# TDT_BreakoutBrd.net
KiCad netlist of a schematic drawn in EAGLE
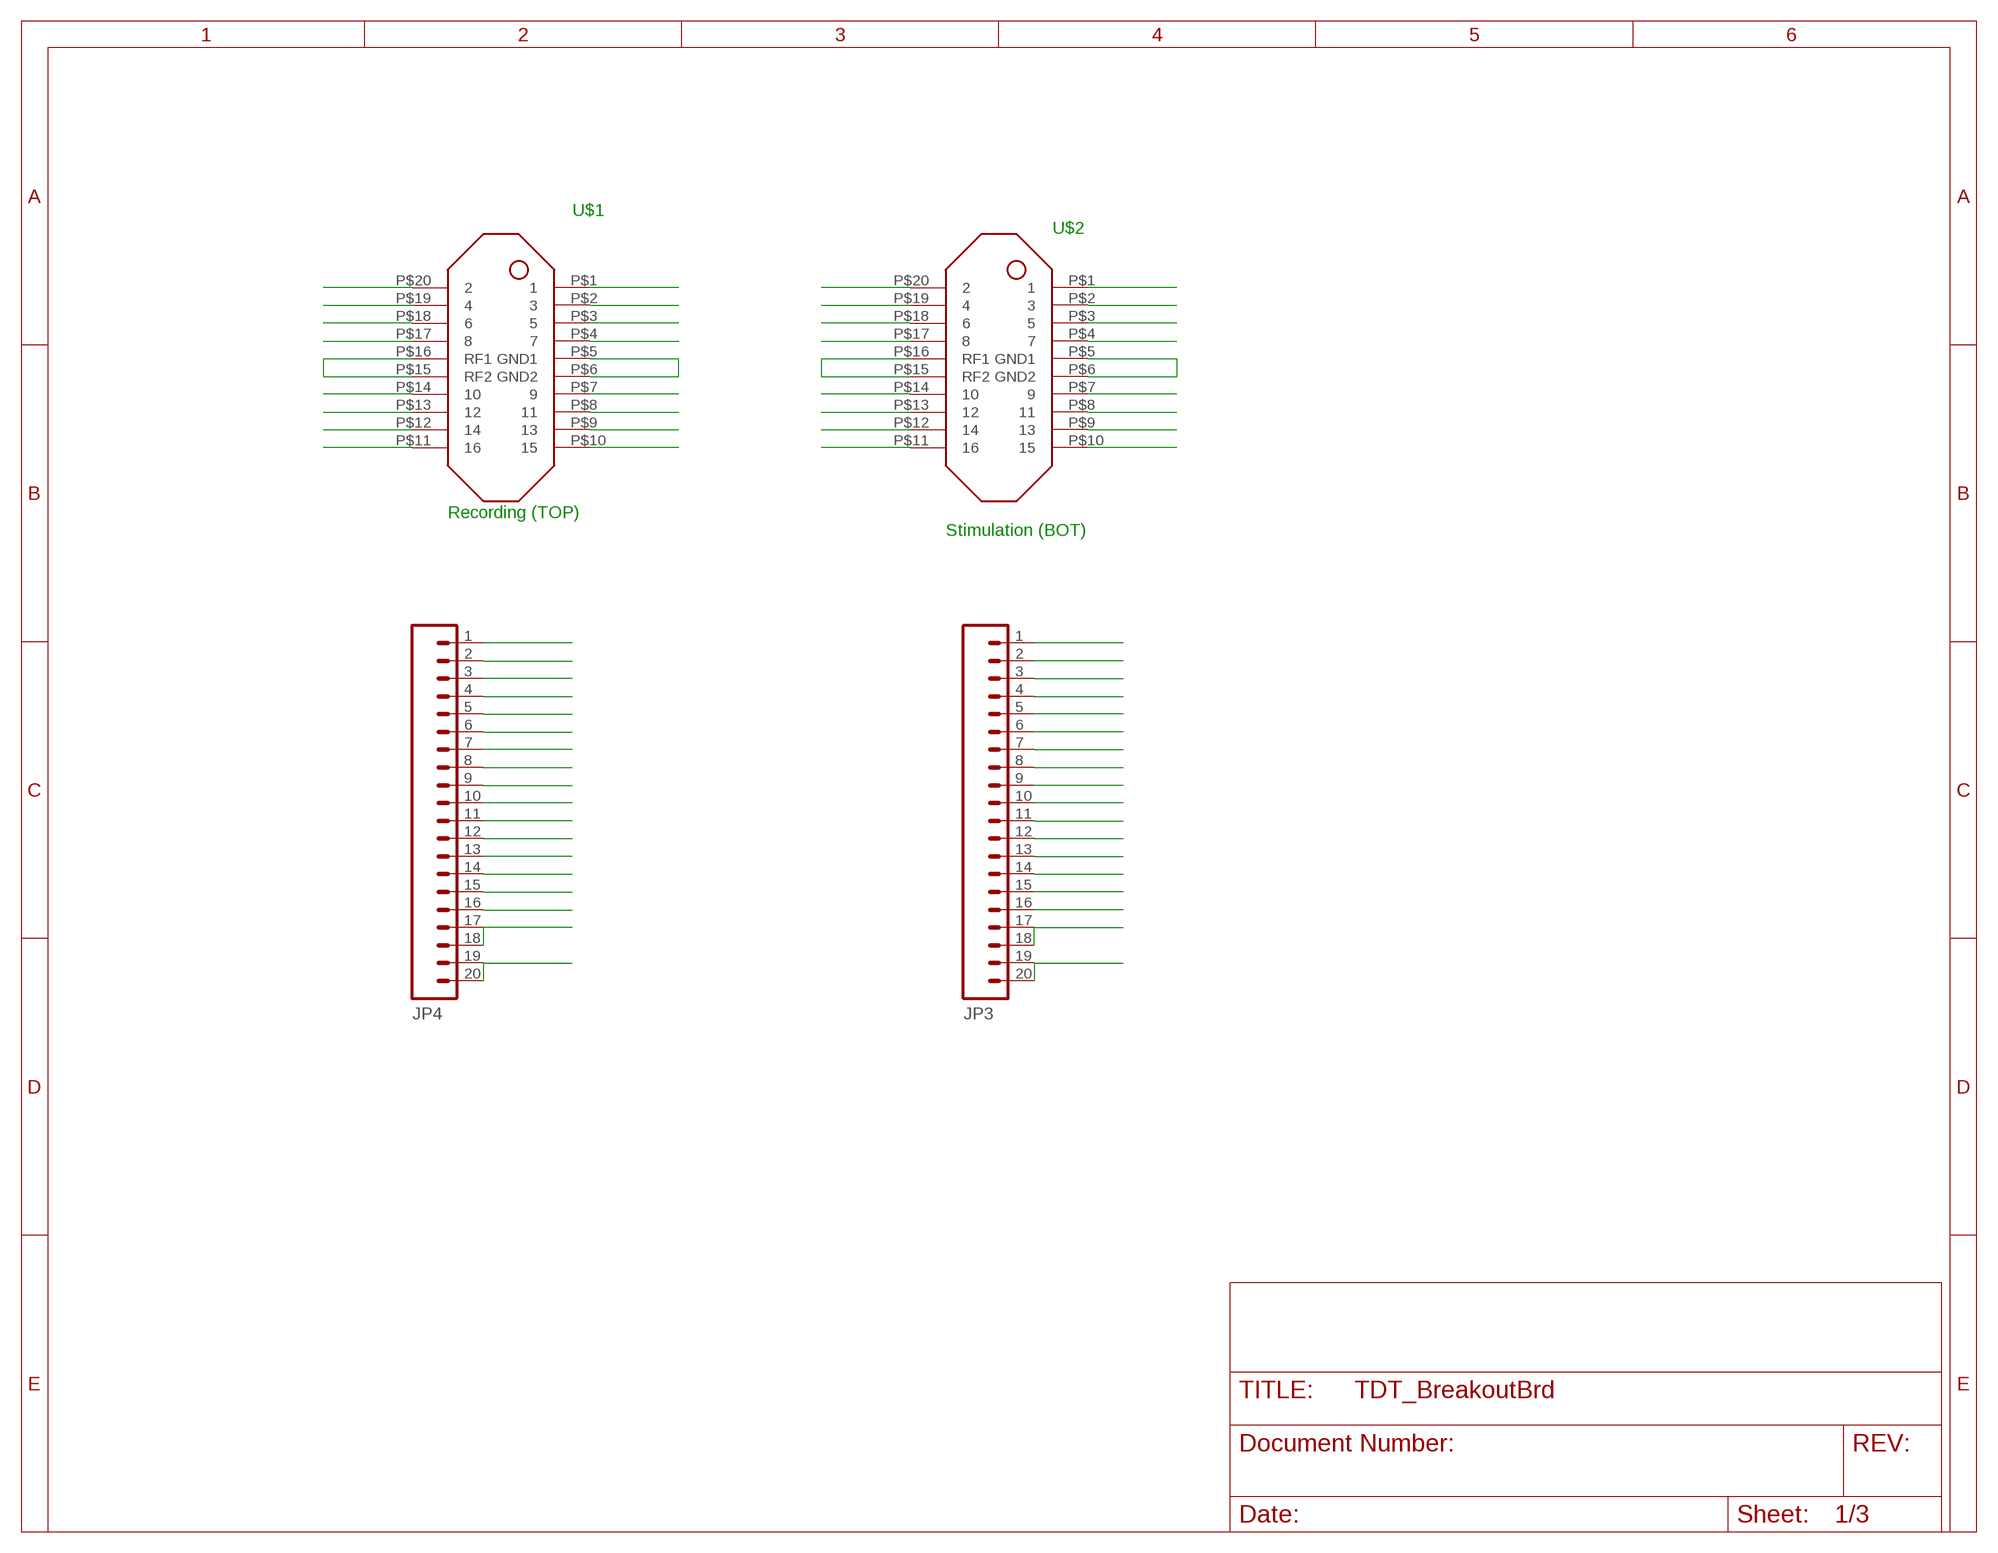
[diagram p0: schematic, sheet 1]

(export (version "E")
  (design (tool "Eeschema 10.0.6"))
  (components
    (comp (ref "JP3")
      (value "M20")
      (footprint "eagle-import:1X20")
      (libsource (lib "eagle-import") (part "M20"))
    )
    (comp (ref "JP4")
      (value "M20")
      (footprint "eagle-import:1X20")
      (libsource (lib "eagle-import") (part "M20"))
    )
    (comp (ref "U$1")
      (value "DF30_HEADER")
      (footprint "eagle-import:DF30FC-20DP-0.4V")
      (libsource (lib "eagle-import") (part "DF30_HEADER"))
    )
    (comp (ref "U$2")
      (value "DF30_HEADER")
      (footprint "eagle-import:DF30FC-20DP-0.4V")
      (libsource (lib "eagle-import") (part "DF30_HEADER"))
    )
  )
  (nets
    (net (code "1") (name "B1") (class "Default")
      (node (ref "JP3") (pin "2") (pinfunction "2_2") (pintype "passive"))
      (node (ref "U$2") (pin "P$1") (pinfunction "1_P$1") (pintype "bidirectional"))
    )
    (net (code "2") (name "B2") (class "Default")
      (node (ref "JP3") (pin "1") (pinfunction "1_1") (pintype "passive"))
      (node (ref "U$2") (pin "P$20") (pinfunction "2_P$20") (pintype "bidirectional"))
    )
    (net (code "3") (name "B3") (class "Default")
      (node (ref "JP3") (pin "4") (pinfunction "4_4") (pintype "passive"))
      (node (ref "U$2") (pin "P$2") (pinfunction "3_P$2") (pintype "bidirectional"))
    )
    (net (code "4") (name "B4") (class "Default")
      (node (ref "JP3") (pin "3") (pinfunction "3_3") (pintype "passive"))
      (node (ref "U$2") (pin "P$19") (pinfunction "4_P$19") (pintype "bidirectional"))
    )
    (net (code "5") (name "B5") (class "Default")
      (node (ref "JP3") (pin "6") (pinfunction "6_6") (pintype "passive"))
      (node (ref "U$2") (pin "P$3") (pinfunction "5_P$3") (pintype "bidirectional"))
    )
    (net (code "6") (name "B6") (class "Default")
      (node (ref "JP3") (pin "5") (pinfunction "5_5") (pintype "passive"))
      (node (ref "U$2") (pin "P$18") (pinfunction "6_P$18") (pintype "bidirectional"))
    )
    (net (code "7") (name "B7") (class "Default")
      (node (ref "JP3") (pin "8") (pinfunction "8_8") (pintype "passive"))
      (node (ref "U$2") (pin "P$4") (pinfunction "7_P$4") (pintype "bidirectional"))
    )
    (net (code "8") (name "B8") (class "Default")
      (node (ref "JP3") (pin "7") (pinfunction "7_7") (pintype "passive"))
      (node (ref "U$2") (pin "P$17") (pinfunction "8_P$17") (pintype "bidirectional"))
    )
    (net (code "9") (name "B9") (class "Default")
      (node (ref "JP3") (pin "10") (pinfunction "10_10") (pintype "passive"))
      (node (ref "U$2") (pin "P$7") (pinfunction "9_P$7") (pintype "bidirectional"))
    )
    (net (code "10") (name "B10") (class "Default")
      (node (ref "JP3") (pin "9") (pinfunction "9_9") (pintype "passive"))
      (node (ref "U$2") (pin "P$14") (pinfunction "10_P$14") (pintype "bidirectional"))
    )
    (net (code "11") (name "B11") (class "Default")
      (node (ref "JP3") (pin "12") (pinfunction "12_12") (pintype "passive"))
      (node (ref "U$2") (pin "P$8") (pinfunction "11_P$8") (pintype "bidirectional"))
    )
    (net (code "12") (name "B12") (class "Default")
      (node (ref "JP3") (pin "11") (pinfunction "11_11") (pintype "passive"))
      (node (ref "U$2") (pin "P$13") (pinfunction "12_P$13") (pintype "bidirectional"))
    )
    (net (code "13") (name "B13") (class "Default")
      (node (ref "JP3") (pin "14") (pinfunction "14_14") (pintype "passive"))
      (node (ref "U$2") (pin "P$9") (pinfunction "13_P$9") (pintype "bidirectional"))
    )
    (net (code "14") (name "B14") (class "Default")
      (node (ref "JP3") (pin "13") (pinfunction "13_13") (pintype "passive"))
      (node (ref "U$2") (pin "P$12") (pinfunction "14_P$12") (pintype "bidirectional"))
    )
    (net (code "15") (name "B15") (class "Default")
      (node (ref "JP3") (pin "16") (pinfunction "16_16") (pintype "passive"))
      (node (ref "U$2") (pin "P$10") (pinfunction "15_P$10") (pintype "bidirectional"))
    )
    (net (code "16") (name "B16") (class "Default")
      (node (ref "JP3") (pin "15") (pinfunction "15_15") (pintype "passive"))
      (node (ref "U$2") (pin "P$11") (pinfunction "16_P$11") (pintype "bidirectional"))
    )
    (net (code "17") (name "BG1") (class "Default")
      (node (ref "JP3") (pin "19") (pinfunction "19_19") (pintype "passive"))
      (node (ref "JP3") (pin "20") (pinfunction "20_20") (pintype "passive"))
      (node (ref "U$2") (pin "P$5") (pinfunction "GND1_P$5") (pintype "bidirectional"))
      (node (ref "U$2") (pin "P$6") (pinfunction "GND2_P$6") (pintype "bidirectional"))
    )
    (net (code "18") (name "BRF1") (class "Default")
      (node (ref "JP3") (pin "17") (pinfunction "17_17") (pintype "passive"))
      (node (ref "JP3") (pin "18") (pinfunction "18_18") (pintype "passive"))
      (node (ref "U$2") (pin "P$15") (pinfunction "RF2_P$15") (pintype "bidirectional"))
      (node (ref "U$2") (pin "P$16") (pinfunction "RF1_P$16") (pintype "bidirectional"))
    )
    (net (code "19") (name "T1") (class "Default")
      (node (ref "JP4") (pin "1") (pinfunction "1_1") (pintype "passive"))
      (node (ref "U$1") (pin "P$1") (pinfunction "1_P$1") (pintype "bidirectional"))
    )
    (net (code "20") (name "T2") (class "Default")
      (node (ref "JP4") (pin "2") (pinfunction "2_2") (pintype "passive"))
      (node (ref "U$1") (pin "P$20") (pinfunction "2_P$20") (pintype "bidirectional"))
    )
    (net (code "21") (name "T3") (class "Default")
      (node (ref "JP4") (pin "3") (pinfunction "3_3") (pintype "passive"))
      (node (ref "U$1") (pin "P$2") (pinfunction "3_P$2") (pintype "bidirectional"))
    )
    (net (code "22") (name "T4") (class "Default")
      (node (ref "JP4") (pin "4") (pinfunction "4_4") (pintype "passive"))
      (node (ref "U$1") (pin "P$19") (pinfunction "4_P$19") (pintype "bidirectional"))
    )
    (net (code "23") (name "T5") (class "Default")
      (node (ref "JP4") (pin "5") (pinfunction "5_5") (pintype "passive"))
      (node (ref "U$1") (pin "P$3") (pinfunction "5_P$3") (pintype "bidirectional"))
    )
    (net (code "24") (name "T6") (class "Default")
      (node (ref "JP4") (pin "6") (pinfunction "6_6") (pintype "passive"))
      (node (ref "U$1") (pin "P$18") (pinfunction "6_P$18") (pintype "bidirectional"))
    )
    (net (code "25") (name "T7") (class "Default")
      (node (ref "JP4") (pin "7") (pinfunction "7_7") (pintype "passive"))
      (node (ref "U$1") (pin "P$4") (pinfunction "7_P$4") (pintype "bidirectional"))
    )
    (net (code "26") (name "T8") (class "Default")
      (node (ref "JP4") (pin "8") (pinfunction "8_8") (pintype "passive"))
      (node (ref "U$1") (pin "P$17") (pinfunction "8_P$17") (pintype "bidirectional"))
    )
    (net (code "27") (name "T9") (class "Default")
      (node (ref "JP4") (pin "9") (pinfunction "9_9") (pintype "passive"))
      (node (ref "U$1") (pin "P$7") (pinfunction "9_P$7") (pintype "bidirectional"))
    )
    (net (code "28") (name "T10") (class "Default")
      (node (ref "JP4") (pin "10") (pinfunction "10_10") (pintype "passive"))
      (node (ref "U$1") (pin "P$14") (pinfunction "10_P$14") (pintype "bidirectional"))
    )
    (net (code "29") (name "T11") (class "Default")
      (node (ref "JP4") (pin "11") (pinfunction "11_11") (pintype "passive"))
      (node (ref "U$1") (pin "P$8") (pinfunction "11_P$8") (pintype "bidirectional"))
    )
    (net (code "30") (name "T12") (class "Default")
      (node (ref "JP4") (pin "12") (pinfunction "12_12") (pintype "passive"))
      (node (ref "U$1") (pin "P$13") (pinfunction "12_P$13") (pintype "bidirectional"))
    )
    (net (code "31") (name "T13") (class "Default")
      (node (ref "JP4") (pin "13") (pinfunction "13_13") (pintype "passive"))
      (node (ref "U$1") (pin "P$9") (pinfunction "13_P$9") (pintype "bidirectional"))
    )
    (net (code "32") (name "T14") (class "Default")
      (node (ref "JP4") (pin "14") (pinfunction "14_14") (pintype "passive"))
      (node (ref "U$1") (pin "P$12") (pinfunction "14_P$12") (pintype "bidirectional"))
    )
    (net (code "33") (name "T15") (class "Default")
      (node (ref "JP4") (pin "15") (pinfunction "15_15") (pintype "passive"))
      (node (ref "U$1") (pin "P$10") (pinfunction "15_P$10") (pintype "bidirectional"))
    )
    (net (code "34") (name "T16") (class "Default")
      (node (ref "JP4") (pin "16") (pinfunction "16_16") (pintype "passive"))
      (node (ref "U$1") (pin "P$11") (pinfunction "16_P$11") (pintype "bidirectional"))
    )
    (net (code "35") (name "TG1") (class "Default")
      (node (ref "JP4") (pin "19") (pinfunction "19_19") (pintype "passive"))
      (node (ref "JP4") (pin "20") (pinfunction "20_20") (pintype "passive"))
      (node (ref "U$1") (pin "P$5") (pinfunction "GND1_P$5") (pintype "bidirectional"))
      (node (ref "U$1") (pin "P$6") (pinfunction "GND2_P$6") (pintype "bidirectional"))
    )
    (net (code "36") (name "TRF1") (class "Default")
      (node (ref "JP4") (pin "17") (pinfunction "17_17") (pintype "passive"))
      (node (ref "JP4") (pin "18") (pinfunction "18_18") (pintype "passive"))
      (node (ref "U$1") (pin "P$15") (pinfunction "RF2_P$15") (pintype "bidirectional"))
      (node (ref "U$1") (pin "P$16") (pinfunction "RF1_P$16") (pintype "bidirectional"))
    )
  )
)
